# 2.net
KiCad netlist of a schematic drawn in Altium Designer
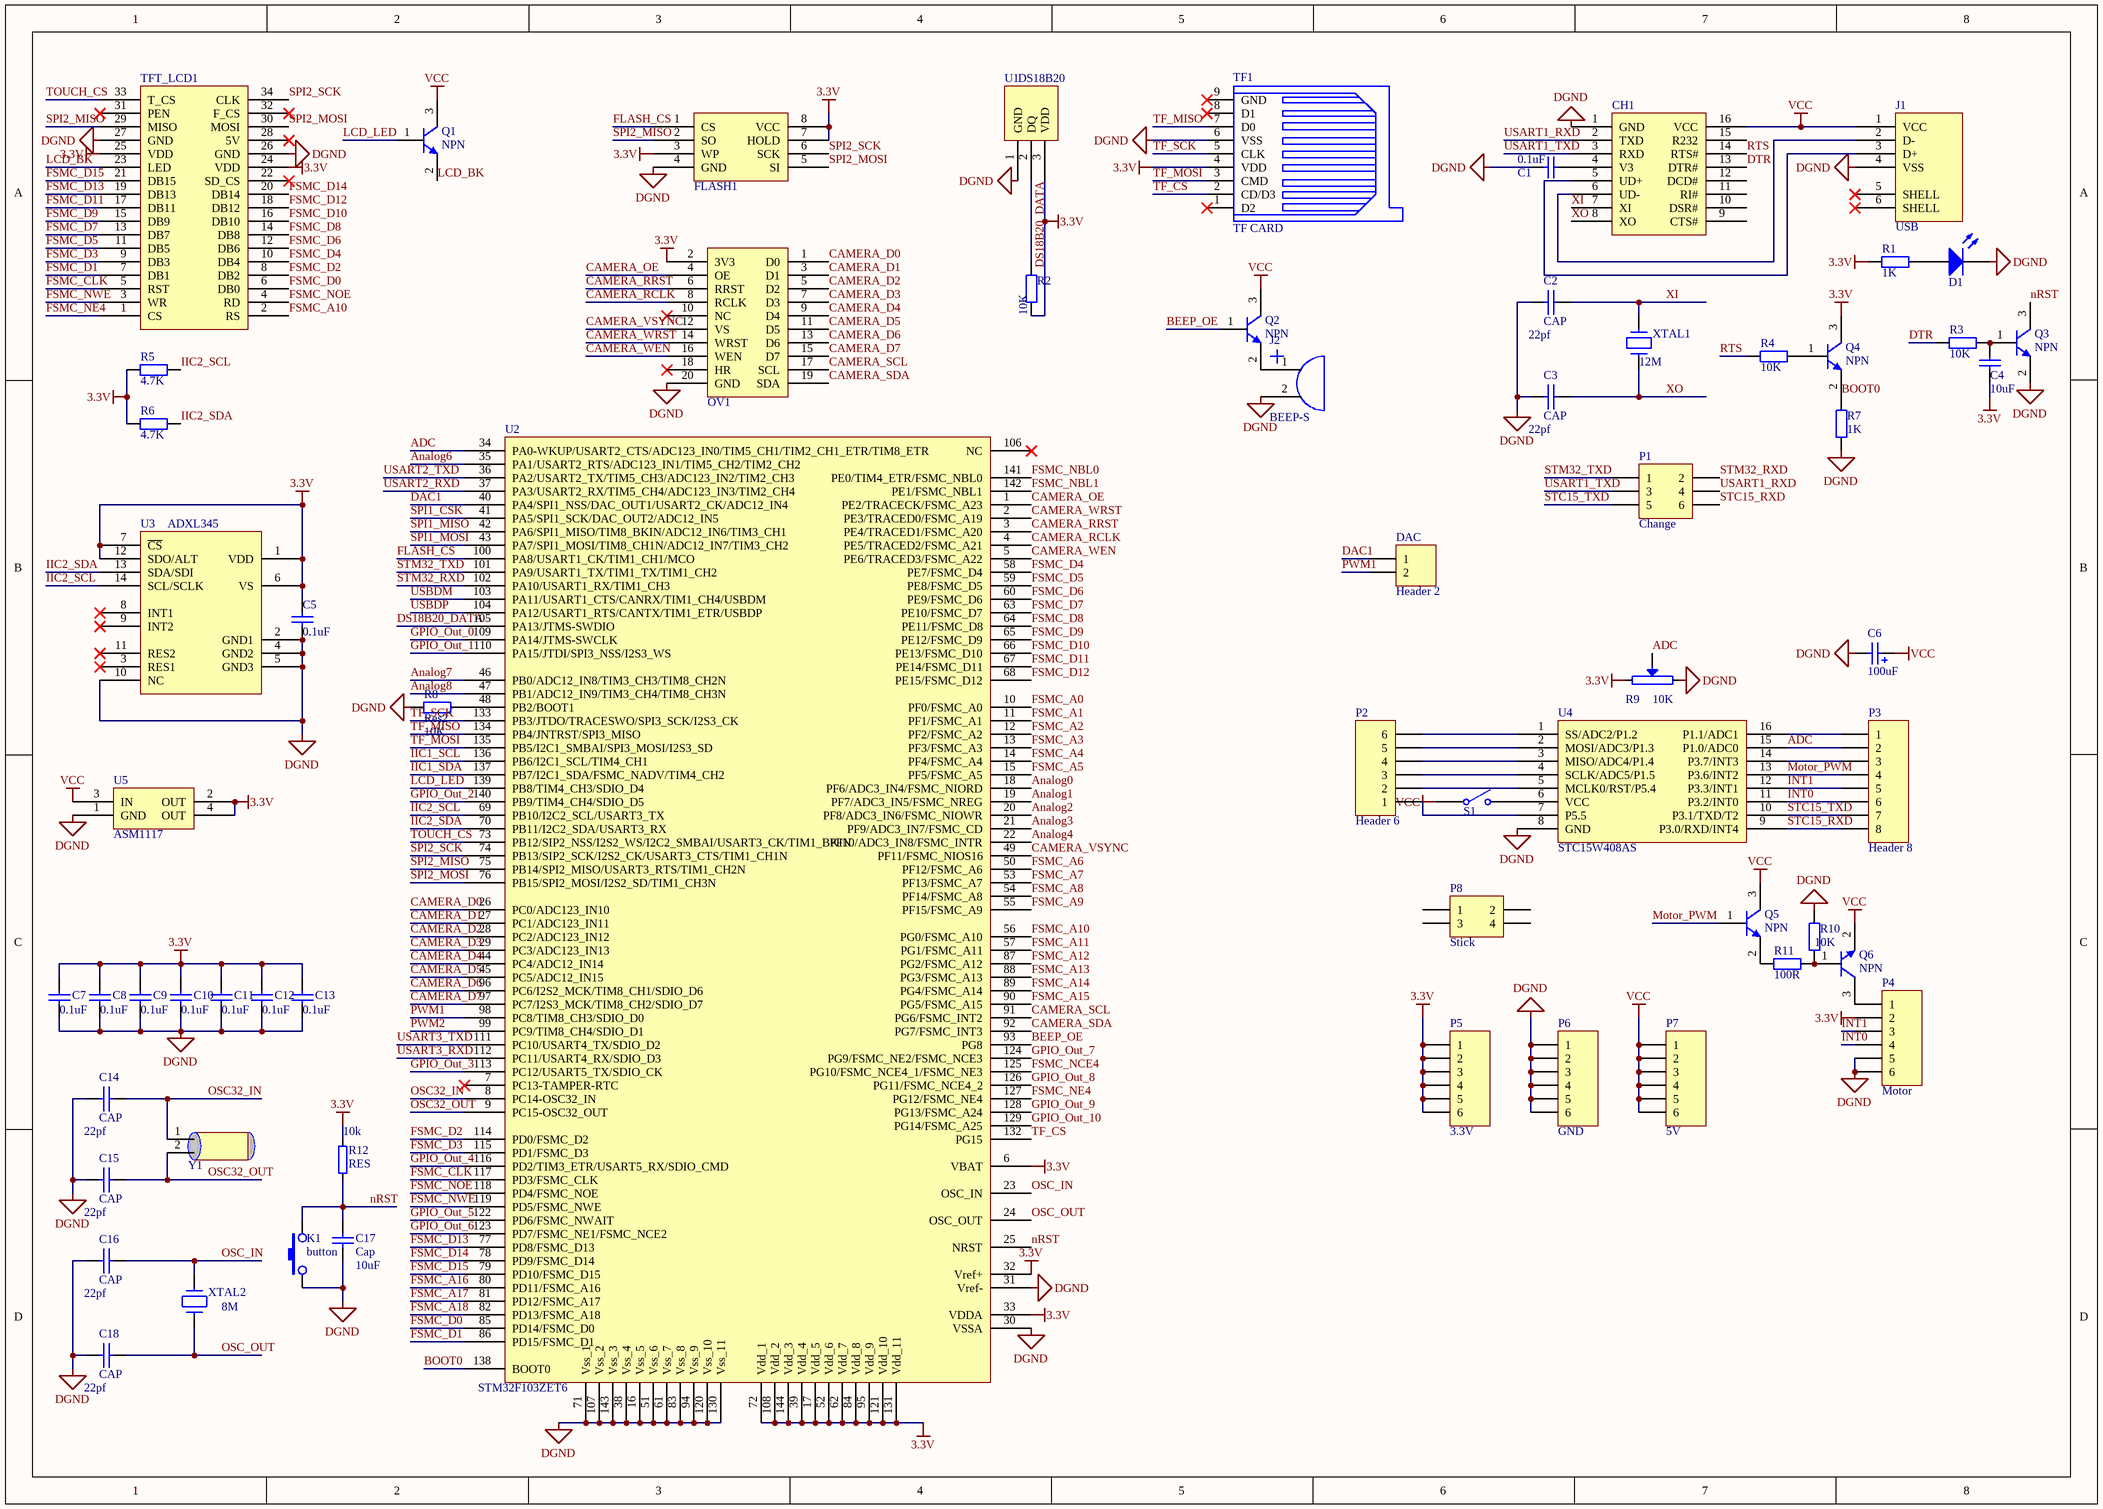
[diagram p0: 测试板2.SchDoc]

(export (version "E")
  (design (tool "Eeschema 10.0.6"))
  (components
    (comp (ref "C1")
      (value "0.1uF")
      (footprint "0805")
      (description "Capacitor")
      (fields (field (name "Comment") "Cap") (field (name "PUBLISHER") "Altium Limited"))
      (libsource (lib "Miscellaneous Devices") (part "Cap"))
    )
    (comp (ref "C2")
      (value "CAP")
      (footprint "0805")
      (fields (field (name "ALTIUM_VALUE") "22pf"))
      (libsource (lib "常用元件库") (part "CAP"))
    )
    (comp (ref "C3")
      (value "CAP")
      (footprint "0805")
      (fields (field (name "ALTIUM_VALUE") "22pf"))
      (libsource (lib "常用元件库") (part "CAP"))
    )
    (comp (ref "C4")
      (value "10uF")
      (footprint "1206")
      (description "Capacitor")
      (fields (field (name "Comment") "Cap") (field (name "PUBLISHER") "Altium Limited"))
      (libsource (lib "Miscellaneous Devices") (part "Cap"))
    )
    (comp (ref "C5")
      (value "0.1uF")
      (footprint "0805")
      (description "Capacitor")
      (fields (field (name "Comment") "Cap") (field (name "PUBLISHER") "Altium Limited"))
      (libsource (lib "Miscellaneous Devices") (part "Cap"))
    )
    (comp (ref "C6")
      (value "100uF")
      (footprint "RB.1/.3")
      (description "Polarized Capacitor (Axial)")
      (fields (field (name "Comment") "Cap Pol2") (field (name "PUBLISHER") "Altium Limited"))
      (libsource (lib "Miscellaneous Devices") (part "Cap Pol2"))
    )
    (comp (ref "C7")
      (value "0.1uF")
      (footprint "0805")
      (description "Capacitor")
      (fields (field (name "Comment") "Cap") (field (name "PUBLISHER") "Altium Limited"))
      (libsource (lib "Miscellaneous Devices") (part "Cap"))
    )
    (comp (ref "C8")
      (value "0.1uF")
      (footprint "0805")
      (description "Capacitor")
      (fields (field (name "Comment") "Cap") (field (name "PUBLISHER") "Altium Limited"))
      (libsource (lib "Miscellaneous Devices") (part "Cap"))
    )
    (comp (ref "C9")
      (value "0.1uF")
      (footprint "0805")
      (description "Capacitor")
      (fields (field (name "Comment") "Cap") (field (name "PUBLISHER") "Altium Limited"))
      (libsource (lib "Miscellaneous Devices") (part "Cap"))
    )
    (comp (ref "C10")
      (value "0.1uF")
      (footprint "0805")
      (description "Capacitor")
      (fields (field (name "Comment") "Cap") (field (name "PUBLISHER") "Altium Limited"))
      (libsource (lib "Miscellaneous Devices") (part "Cap"))
    )
    (comp (ref "C11")
      (value "0.1uF")
      (footprint "0805")
      (description "Capacitor")
      (fields (field (name "Comment") "Cap") (field (name "PUBLISHER") "Altium Limited"))
      (libsource (lib "Miscellaneous Devices") (part "Cap"))
    )
    (comp (ref "C12")
      (value "0.1uF")
      (footprint "0805")
      (description "Capacitor")
      (fields (field (name "Comment") "Cap") (field (name "PUBLISHER") "Altium Limited"))
      (libsource (lib "Miscellaneous Devices") (part "Cap"))
    )
    (comp (ref "C13")
      (value "0.1uF")
      (footprint "0805")
      (description "Capacitor")
      (fields (field (name "Comment") "Cap") (field (name "PUBLISHER") "Altium Limited"))
      (libsource (lib "Miscellaneous Devices") (part "Cap"))
    )
    (comp (ref "C14")
      (value "CAP")
      (footprint "0805")
      (fields (field (name "ALTIUM_VALUE") "22pf"))
      (libsource (lib "常用元件库") (part "CAP"))
    )
    (comp (ref "C15")
      (value "CAP")
      (footprint "0805")
      (fields (field (name "ALTIUM_VALUE") "22pf"))
      (libsource (lib "常用元件库") (part "CAP"))
    )
    (comp (ref "C16")
      (value "CAP")
      (footprint "0805")
      (fields (field (name "ALTIUM_VALUE") "22pf"))
      (libsource (lib "常用元件库") (part "CAP"))
    )
    (comp (ref "C17")
      (value "Cap")
      (footprint "1206")
      (description "Capacitor")
      (fields (field (name "ALTIUM_VALUE") "10uF") (field (name "PUBLISHER") "Altium Limited"))
      (libsource (lib "Miscellaneous Devices") (part "Cap"))
    )
    (comp (ref "C18")
      (value "CAP")
      (footprint "0805")
      (fields (field (name "ALTIUM_VALUE") "22pf"))
      (libsource (lib "常用元件库") (part "CAP"))
    )
    (comp (ref "CH1")
      (value "Component_1")
      (footprint "SOIC127P600X170-16N")
      (libsource (lib "CH340G") (part "Component_1"))
    )
    (comp (ref "D1")
      (value "LED0")
      (footprint "LED-0805")
      (description "发光二极管")
      (fields (field (name "PUBLISHER") "Altium Limited"))
      (libsource (lib "fszhang") (part "LED0"))
    )
    (comp (ref "DAC")
      (value "Header 2")
      (footprint "HDR1X2")
      (description "Header, 2-Pin")
      (fields (field (name "PUBLISHER") "Altium Limited"))
      (libsource (lib "Miscellaneous Connectors") (part "Header 2"))
    )
    (comp (ref "FLASH1") (value "W25Q64") (footprint "8S2_L") (libsource (lib "显示屏及摄像头") (part "W25Q64")))
    (comp (ref "J1")
      (value "USB")
      (footprint "USB_B1")
      (description "USB接口")
      (libsource (lib "HDR_fszhang") (part "USB"))
    )
    (comp (ref "J2")
      (value "BEEP-S")
      (footprint "BEEP-S")
      (description "有源蜂鸣器")
      (libsource (lib "fszhang") (part "BEEP-S"))
    )
    (comp (ref "K1") (value "button") (footprint "SW_PB4_A1") (libsource (lib "my Library") (part "button")))
    (comp (ref "OV1")
      (value "OV7725摄像头")
      (footprint "HDR2X10")
      (libsource (lib "显示屏及摄像头") (part "OV7725摄像头"))
    )
    (comp (ref "P1")
      (value "Change")
      (footprint "HDR2X3")
      (description "Header, 3-Pin, Dual row")
      (fields (field (name "PUBLISHER") "Altium Limited"))
      (libsource (lib "Miscellaneous Connectors") (part "Header 3X2"))
    )
    (comp (ref "P2")
      (value "Header 6")
      (footprint "HDR1X6")
      (description "Header, 6-Pin")
      (fields (field (name "PUBLISHER") "Altium Limited"))
      (libsource (lib "") (part "Header 6_1"))
    )
    (comp (ref "P3")
      (value "Header 8")
      (footprint "HDR1X8")
      (description "Header, 8-Pin")
      (fields (field (name "PUBLISHER") "Altium Limited"))
      (libsource (lib "Miscellaneous Connectors") (part "Header 8"))
    )
    (comp (ref "P4")
      (value "Motor")
      (footprint "HDR1X6")
      (description "Header, 6-Pin")
      (fields (field (name "PUBLISHER") "Altium Limited"))
      (libsource (lib "Miscellaneous Connectors") (part "Header 6"))
    )
    (comp (ref "P5")
      (value "3.3V")
      (footprint "HDR1X6")
      (description "Header, 6-Pin")
      (fields (field (name "PUBLISHER") "Altium Limited"))
      (libsource (lib "Miscellaneous Connectors") (part "Header 6"))
    )
    (comp (ref "P6")
      (value "GND")
      (footprint "HDR1X6")
      (description "Header, 6-Pin")
      (fields (field (name "PUBLISHER") "Altium Limited"))
      (libsource (lib "Miscellaneous Connectors") (part "Header 6"))
    )
    (comp (ref "P7")
      (value "5V")
      (footprint "HDR1X6")
      (description "Header, 6-Pin")
      (fields (field (name "PUBLISHER") "Altium Limited"))
      (libsource (lib "Miscellaneous Connectors") (part "Header 6"))
    )
    (comp (ref "P8")
      (value "Stick")
      (footprint "HDR2X2")
      (description "Header, 2-Pin, Dual row")
      (fields (field (name "PUBLISHER") "Altium Limited"))
      (libsource (lib "Miscellaneous Connectors") (part "Header 2X2"))
    )
    (comp (ref "Q1")
      (value "NPN")
      (footprint "SOT23-3")
      (description "贴片三极管")
      (fields (field (name "PUBLISHER") "Altium Limited"))
      (libsource (lib "fszhang") (part "NPN1"))
    )
    (comp (ref "Q2")
      (value "NPN")
      (footprint "SOT23-3")
      (description "贴片三极管")
      (fields (field (name "PUBLISHER") "Altium Limited"))
      (libsource (lib "fszhang") (part "NPN1"))
    )
    (comp (ref "Q3")
      (value "NPN")
      (footprint "SOT23-3")
      (description "贴片三极管")
      (fields (field (name "PUBLISHER") "Altium Limited"))
      (libsource (lib "fszhang") (part "NPN1"))
    )
    (comp (ref "Q4")
      (value "NPN")
      (footprint "SOT23-3")
      (description "贴片三极管")
      (fields (field (name "PUBLISHER") "Altium Limited"))
      (libsource (lib "fszhang") (part "NPN1"))
    )
    (comp (ref "Q5")
      (value "NPN")
      (footprint "SOT23-3")
      (description "贴片三极管")
      (fields (field (name "PUBLISHER") "Altium Limited"))
      (libsource (lib "fszhang") (part "NPN1"))
    )
    (comp (ref "Q6")
      (value "NPN")
      (footprint "SOT89N")
      (description "贴片三极管")
      (fields (field (name "PUBLISHER") "Altium Limited"))
      (libsource (lib "fszhang") (part "NPN1"))
    )
    (comp (ref "R1")
      (value "1K")
      (footprint "0805")
      (description "Resistor")
      (fields (field (name "Comment") "Res2") (field (name "PUBLISHER") "Altium Limited"))
      (libsource (lib "Miscellaneous Devices") (part "Res2"))
    )
    (comp (ref "R2")
      (value "10K")
      (footprint "0805")
      (description "Resistor")
      (fields (field (name "Comment") "Res2") (field (name "PUBLISHER") "Altium Limited"))
      (libsource (lib "") (part "Res2_1"))
    )
    (comp (ref "R3")
      (value "10K")
      (footprint "0805")
      (description "Resistor")
      (fields (field (name "Comment") "Res2") (field (name "PUBLISHER") "Altium Limited"))
      (libsource (lib "") (part "Res2_2"))
    )
    (comp (ref "R4")
      (value "10K")
      (footprint "0805")
      (description "Resistor")
      (fields (field (name "Comment") "Res2") (field (name "PUBLISHER") "Altium Limited"))
      (libsource (lib "") (part "Res2_2"))
    )
    (comp (ref "R5")
      (value "4.7K")
      (footprint "0805")
      (description "Resistor")
      (fields (field (name "Comment") "Res2") (field (name "PUBLISHER") "Altium Limited"))
      (libsource (lib "Miscellaneous Devices") (part "Res2"))
    )
    (comp (ref "R6")
      (value "4.7K")
      (footprint "0805")
      (description "Resistor")
      (fields (field (name "Comment") "Res2") (field (name "PUBLISHER") "Altium Limited"))
      (libsource (lib "Miscellaneous Devices") (part "Res2"))
    )
    (comp (ref "R7")
      (value "1K")
      (footprint "0805")
      (description "Resistor")
      (fields (field (name "Comment") "Res2") (field (name "PUBLISHER") "Altium Limited"))
      (libsource (lib "") (part "Res2_1"))
    )
    (comp (ref "R8")
      (value "Res2")
      (footprint "0805")
      (description "Resistor")
      (fields (field (name "ALTIUM_VALUE") "10K") (field (name "PUBLISHER") "Altium Limited"))
      (libsource (lib "Miscellaneous Devices") (part "Res2"))
    )
    (comp (ref "R9") (value "10K") (footprint "RVR-2") (libsource (lib "常用元件库") (part "VR")))
    (comp (ref "R10")
      (value "10K")
      (footprint "0805")
      (description "Resistor")
      (fields (field (name "Comment") "Res2") (field (name "PUBLISHER") "Altium Limited"))
      (libsource (lib "") (part "Res2_3"))
    )
    (comp (ref "R11")
      (value "100R")
      (footprint "0805")
      (description "Resistor")
      (fields (field (name "Comment") "Res2") (field (name "PUBLISHER") "Altium Limited"))
      (libsource (lib "Miscellaneous Devices") (part "Res2"))
    )
    (comp (ref "R12")
      (value "RES")
      (footprint "0805")
      (fields (field (name "ALTIUM_VALUE") "10k"))
      (libsource (lib "电阻") (part "RES"))
    )
    (comp (ref "S1")
      (value "SW-SPST")
      (footprint "SWITCH_B1")
      (description "Single-Pole, Single-Throw Switch")
      (fields (field (name "PUBLISHER") "Altium Limited"))
      (libsource (lib "Miscellaneous Devices") (part "SW-SPST"))
    )
    (comp (ref "TF1")
      (value "TF CARD")
      (footprint "TFP09-2-12B")
      (libsource (lib "My Footprint") (part "TF CARD"))
    )
    (comp (ref "TFT_LCD1")
      (value "Component_1")
      (footprint "HDR2X17")
      (libsource (lib "显示屏") (part "Component_1"))
    )
    (comp (ref "U1")
      (value "DS18B20")
      (footprint "TO-92A")
      (description "温度传感器")
      (libsource (lib "fszhang") (part "DS18B20"))
    )
    (comp (ref "U2")
      (value "STM32F103ZET6")
      (footprint "TQFP-144")
      (libsource (lib "STM32F103ZET6") (part "STM32F103ZET6"))
    )
    (comp (ref "U3")
      (value "ADXL345")
      (footprint "ADXL345:PCBComponent_1")
      (libsource (lib "ADXL345") (part "ADXL345"))
    )
    (comp (ref "U4")
      (value "STC15W408AS")
      (footprint "SOIC127P600X170-16N")
      (libsource (lib "显示屏及摄像头") (part "STC15W408AS"))
    )
    (comp (ref "U5")
      (value "ASM1117")
      (footprint "SOT223")
      (description "3.3V稳压芯片")
      (libsource (lib "fszhang") (part "ASM1117"))
    )
    (comp (ref "XTAL1")
      (value "12M")
      (footprint "X-SM49")
      (fields (field (name "Comment") "CRYSTAL"))
      (libsource (lib "常用元件库") (part "CRYSTAL"))
    )
    (comp (ref "XTAL2")
      (value "8M")
      (footprint "X-SM49")
      (fields (field (name "Comment") "CRYSTAL"))
      (libsource (lib "常用元件库") (part "CRYSTAL"))
    )
    (comp (ref "Y1") (value "32K晶振") (footprint "X-TC15") (libsource (lib "Library 1") (part "32K晶振")))
  )
  (nets
    (net (code "1") (name "/ADC") (class "Default")
      (node (ref "P3") (pin "2") (pinfunction "2_2") (pintype "passive"))
      (node (ref "R9") (pin "W") (pintype "passive"))
      (node (ref "U2") (pin "34") (pinfunction "PA0-WKUP/USART2_CTS/ADC123_IN0/TIM5_CH1/TIM2_CH1_ETR/TIM8_ETR_34") (pintype "passive"))
      (node (ref "U4") (pin "15") (pinfunction "P1.0/ADC0_15") (pintype "passive"))
    )
    (net (code "2") (name "/Analog0") (class "Default")
      (node (ref "U2") (pin "18") (pinfunction "PF6/ADC3_IN4/FSMC_NIORD_18") (pintype "passive"))
    )
    (net (code "3") (name "/Analog1") (class "Default")
      (node (ref "U2") (pin "19") (pinfunction "PF7/ADC3_IN5/FSMC_NREG_19") (pintype "passive"))
    )
    (net (code "4") (name "/Analog2") (class "Default")
      (node (ref "U2") (pin "20") (pinfunction "PF8/ADC3_IN6/FSMC_NIOWR_20") (pintype "passive"))
    )
    (net (code "5") (name "/Analog3") (class "Default")
      (node (ref "U2") (pin "21") (pinfunction "PF9/ADC3_IN7/FSMC_CD_21") (pintype "passive"))
    )
    (net (code "6") (name "/Analog4") (class "Default")
      (node (ref "U2") (pin "22") (pinfunction "PF10/ADC3_IN8/FSMC_INTR_22") (pintype "passive"))
    )
    (net (code "7") (name "/Analog6") (class "Default")
      (node (ref "U2") (pin "35") (pinfunction "PA1/USART2_RTS/ADC123_IN1/TIM5_CH2/TIM2_CH2_35") (pintype "passive"))
    )
    (net (code "8") (name "/Analog7") (class "Default")
      (node (ref "U2") (pin "46") (pinfunction "PB0/ADC12_IN8/TIM3_CH3/TIM8_CH2N_46") (pintype "passive"))
    )
    (net (code "9") (name "/Analog8") (class "Default")
      (node (ref "U2") (pin "47") (pinfunction "PB1/ADC12_IN9/TIM3_CH4/TIM8_CH3N_47") (pintype "passive"))
    )
    (net (code "10") (name "/BEEP_OE") (class "Default")
      (node (ref "Q2") (pin "1") (pinfunction "B_1") (pintype "passive"))
      (node (ref "U2") (pin "93") (pinfunction "PG8_93") (pintype "passive"))
    )
    (net (code "11") (name "/BOOT0") (class "Default")
      (node (ref "Q4") (pin "2") (pinfunction "E_2") (pintype "passive"))
      (node (ref "R7") (pin "2") (pinfunction "2_2") (pintype "passive"))
      (node (ref "U2") (pin "138") (pinfunction "BOOT0_138") (pintype "passive"))
    )
    (net (code "12") (name "/CAMERA_D0") (class "Default")
      (node (ref "OV1") (pin "1") (pinfunction "D0_1") (pintype "passive"))
      (node (ref "U2") (pin "26") (pinfunction "PC0/ADC123_IN10_26") (pintype "passive"))
    )
    (net (code "13") (name "/CAMERA_D1") (class "Default")
      (node (ref "OV1") (pin "3") (pinfunction "D1_3") (pintype "passive"))
      (node (ref "U2") (pin "27") (pinfunction "PC1/ADC123_IN11_27") (pintype "passive"))
    )
    (net (code "14") (name "/CAMERA_D2") (class "Default")
      (node (ref "OV1") (pin "5") (pinfunction "D2_5") (pintype "passive"))
      (node (ref "U2") (pin "28") (pinfunction "PC2/ADC123_IN12_28") (pintype "passive"))
    )
    (net (code "15") (name "/CAMERA_D3") (class "Default")
      (node (ref "OV1") (pin "7") (pinfunction "D3_7") (pintype "passive"))
      (node (ref "U2") (pin "29") (pinfunction "PC3/ADC123_IN13_29") (pintype "passive"))
    )
    (net (code "16") (name "/CAMERA_D4") (class "Default")
      (node (ref "OV1") (pin "9") (pinfunction "D4_9") (pintype "passive"))
      (node (ref "U2") (pin "44") (pinfunction "PC4/ADC12_IN14_44") (pintype "passive"))
    )
    (net (code "17") (name "/CAMERA_D5") (class "Default")
      (node (ref "OV1") (pin "11") (pinfunction "D5_11") (pintype "passive"))
      (node (ref "U2") (pin "45") (pinfunction "PC5/ADC12_IN15_45") (pintype "passive"))
    )
    (net (code "18") (name "/CAMERA_D6") (class "Default")
      (node (ref "OV1") (pin "13") (pinfunction "D6_13") (pintype "passive"))
      (node (ref "U2") (pin "96") (pinfunction "PC6/I2S2_MCK/TIM8_CH1/SDIO_D6_96") (pintype "passive"))
    )
    (net (code "19") (name "/CAMERA_D7") (class "Default")
      (node (ref "OV1") (pin "15") (pinfunction "D7_15") (pintype "passive"))
      (node (ref "U2") (pin "97") (pinfunction "PC7/I2S3_MCK/TIM8_CH2/SDIO_D7_97") (pintype "passive"))
    )
    (net (code "20") (name "/CAMERA_OE") (class "Default")
      (node (ref "OV1") (pin "4") (pinfunction "OE_4") (pintype "passive"))
      (node (ref "U2") (pin "1") (pinfunction "PE2/TRACECK/FSMC_A23_1") (pintype "passive"))
    )
    (net (code "21") (name "/CAMERA_RCLK") (class "Default")
      (node (ref "OV1") (pin "8") (pinfunction "RCLK_8") (pintype "passive"))
      (node (ref "U2") (pin "4") (pinfunction "PE5/TRACED2/FSMC_A21_4") (pintype "passive"))
    )
    (net (code "22") (name "/CAMERA_RRST") (class "Default")
      (node (ref "OV1") (pin "6") (pinfunction "RRST_6") (pintype "passive"))
      (node (ref "U2") (pin "3") (pinfunction "PE4/TRACED1/FSMC_A20_3") (pintype "passive"))
    )
    (net (code "23") (name "/CAMERA_SCL") (class "Default")
      (node (ref "OV1") (pin "17") (pinfunction "SCL_17") (pintype "passive"))
      (node (ref "U2") (pin "91") (pinfunction "PG6/FSMC_INT2_91") (pintype "passive"))
    )
    (net (code "24") (name "/CAMERA_SDA") (class "Default")
      (node (ref "OV1") (pin "19") (pinfunction "SDA_19") (pintype "passive"))
      (node (ref "U2") (pin "92") (pinfunction "PG7/FSMC_INT3_92") (pintype "passive"))
    )
    (net (code "25") (name "/CAMERA_VSYNC") (class "Default")
      (node (ref "OV1") (pin "12") (pinfunction "VS_12") (pintype "passive"))
      (node (ref "U2") (pin "49") (pinfunction "PF11/FSMC_NIOS16_49") (pintype "passive"))
    )
    (net (code "26") (name "/CAMERA_WEN") (class "Default")
      (node (ref "OV1") (pin "16") (pinfunction "WEN_16") (pintype "passive"))
      (node (ref "U2") (pin "5") (pinfunction "PE6/TRACED3/FSMC_A22_5") (pintype "passive"))
    )
    (net (code "27") (name "/CAMERA_WRST") (class "Default")
      (node (ref "OV1") (pin "14") (pinfunction "WRST_14") (pintype "passive"))
      (node (ref "U2") (pin "2") (pinfunction "PE3/TRACED0/FSMC_A19_2") (pintype "passive"))
    )
    (net (code "28") (name "/DAC1") (class "Default")
      (node (ref "DAC") (pin "1") (pinfunction "1_1") (pintype "passive"))
      (node (ref "U2") (pin "40") (pinfunction "PA4/SPI1_NSS/DAC_OUT1/USART2_CK/ADC12_IN4_40") (pintype "passive"))
    )
    (net (code "29") (name "/DS18B20_DATA") (class "Default")
      (node (ref "R2") (pin "2") (pinfunction "2_2") (pintype "passive"))
      (node (ref "U1") (pin "2") (pinfunction "DQ_2") (pintype "passive"))
      (node (ref "U2") (pin "105") (pinfunction "PA13/JTMS-SWDIO_105") (pintype "passive"))
    )
    (net (code "30") (name "/DTR") (class "Default")
      (node (ref "CH1") (pin "13") (pinfunction "DTR#_13") (pintype "passive"))
      (node (ref "R3") (pin "2") (pinfunction "2_2") (pintype "passive"))
    )
    (net (code "31") (name "/FLASH_CS") (class "Default")
      (node (ref "FLASH1") (pin "1") (pinfunction "CS_1") (pintype "passive"))
      (node (ref "U2") (pin "100") (pinfunction "PA8/USART1_CK/TIM1_CH1/MCO_100") (pintype "passive"))
    )
    (net (code "32") (name "/FSMC_A0") (class "Default")
      (node (ref "U2") (pin "10") (pinfunction "PF0/FSMC_A0_10") (pintype "passive"))
    )
    (net (code "33") (name "/FSMC_A1") (class "Default")
      (node (ref "U2") (pin "11") (pinfunction "PF1/FSMC_A1_11") (pintype "passive"))
    )
    (net (code "34") (name "/FSMC_A2") (class "Default")
      (node (ref "U2") (pin "12") (pinfunction "PF2/FSMC_A2_12") (pintype "passive"))
    )
    (net (code "35") (name "/FSMC_A3") (class "Default")
      (node (ref "U2") (pin "13") (pinfunction "PF3/FSMC_A3_13") (pintype "passive"))
    )
    (net (code "36") (name "/FSMC_A4") (class "Default")
      (node (ref "U2") (pin "14") (pinfunction "PF4/FSMC_A4_14") (pintype "passive"))
    )
    (net (code "37") (name "/FSMC_A5") (class "Default")
      (node (ref "U2") (pin "15") (pinfunction "PF5/FSMC_A5_15") (pintype "passive"))
    )
    (net (code "38") (name "/FSMC_A6") (class "Default")
      (node (ref "U2") (pin "50") (pinfunction "PF12/FSMC_A6_50") (pintype "passive"))
    )
    (net (code "39") (name "/FSMC_A7") (class "Default")
      (node (ref "U2") (pin "53") (pinfunction "PF13/FSMC_A7_53") (pintype "passive"))
    )
    (net (code "40") (name "/FSMC_A8") (class "Default")
      (node (ref "U2") (pin "54") (pinfunction "PF14/FSMC_A8_54") (pintype "passive"))
    )
    (net (code "41") (name "/FSMC_A9") (class "Default")
      (node (ref "U2") (pin "55") (pinfunction "PF15/FSMC_A9_55") (pintype "passive"))
    )
    (net (code "42") (name "/FSMC_A10") (class "Default")
      (node (ref "TFT_LCD1") (pin "2") (pinfunction "RS_2") (pintype "passive"))
      (node (ref "U2") (pin "56") (pinfunction "PG0/FSMC_A10_56") (pintype "passive"))
    )
    (net (code "43") (name "/FSMC_A11") (class "Default")
      (node (ref "U2") (pin "57") (pinfunction "PG1/FSMC_A11_57") (pintype "passive"))
    )
    (net (code "44") (name "/FSMC_A12") (class "Default")
      (node (ref "U2") (pin "87") (pinfunction "PG2/FSMC_A12_87") (pintype "passive"))
    )
    (net (code "45") (name "/FSMC_A13") (class "Default")
      (node (ref "U2") (pin "88") (pinfunction "PG3/FSMC_A13_88") (pintype "passive"))
    )
    (net (code "46") (name "/FSMC_A14") (class "Default")
      (node (ref "U2") (pin "89") (pinfunction "PG4/FSMC_A14_89") (pintype "passive"))
    )
    (net (code "47") (name "/FSMC_A15") (class "Default")
      (node (ref "U2") (pin "90") (pinfunction "PG5/FSMC_A15_90") (pintype "passive"))
    )
    (net (code "48") (name "/FSMC_A16") (class "Default")
      (node (ref "U2") (pin "80") (pinfunction "PD11/FSMC_A16_80") (pintype "passive"))
    )
    (net (code "49") (name "/FSMC_A17") (class "Default")
      (node (ref "U2") (pin "81") (pinfunction "PD12/FSMC_A17_81") (pintype "passive"))
    )
    (net (code "50") (name "/FSMC_A18") (class "Default")
      (node (ref "U2") (pin "82") (pinfunction "PD13/FSMC_A18_82") (pintype "passive"))
    )
    (net (code "51") (name "/FSMC_CLK") (class "Default")
      (node (ref "TFT_LCD1") (pin "5") (pinfunction "RST_5") (pintype "passive"))
      (node (ref "U2") (pin "117") (pinfunction "PD3/FSMC_CLK_117") (pintype "passive"))
    )
    (net (code "52") (name "/FSMC_D0") (class "Default")
      (node (ref "TFT_LCD1") (pin "6") (pinfunction "DB0_6") (pintype "passive"))
      (node (ref "U2") (pin "85") (pinfunction "PD14/FSMC_D0_85") (pintype "passive"))
    )
    (net (code "53") (name "/FSMC_D1") (class "Default")
      (node (ref "TFT_LCD1") (pin "7") (pinfunction "DB1_7") (pintype "passive"))
      (node (ref "U2") (pin "86") (pinfunction "PD15/FSMC_D1_86") (pintype "passive"))
    )
    (net (code "54") (name "/FSMC_D2") (class "Default")
      (node (ref "TFT_LCD1") (pin "8") (pinfunction "DB2_8") (pintype "passive"))
      (node (ref "U2") (pin "114") (pinfunction "PD0/FSMC_D2_114") (pintype "passive"))
    )
    (net (code "55") (name "/FSMC_D3") (class "Default")
      (node (ref "TFT_LCD1") (pin "9") (pinfunction "DB3_9") (pintype "passive"))
      (node (ref "U2") (pin "115") (pinfunction "PD1/FSMC_D3_115") (pintype "passive"))
    )
    (net (code "56") (name "/FSMC_D4") (class "Default")
      (node (ref "TFT_LCD1") (pin "10") (pinfunction "DB4_10") (pintype "passive"))
      (node (ref "U2") (pin "58") (pinfunction "PE7/FSMC_D4_58") (pintype "passive"))
    )
    (net (code "57") (name "/FSMC_D5") (class "Default")
      (node (ref "TFT_LCD1") (pin "11") (pinfunction "DB5_11") (pintype "passive"))
      (node (ref "U2") (pin "59") (pinfunction "PE8/FSMC_D5_59") (pintype "passive"))
    )
    (net (code "58") (name "/FSMC_D6") (class "Default")
      (node (ref "TFT_LCD1") (pin "12") (pinfunction "DB6_12") (pintype "passive"))
      (node (ref "U2") (pin "60") (pinfunction "PE9/FSMC_D6_60") (pintype "passive"))
    )
    (net (code "59") (name "/FSMC_D7") (class "Default")
      (node (ref "TFT_LCD1") (pin "13") (pinfunction "DB7_13") (pintype "passive"))
      (node (ref "U2") (pin "63") (pinfunction "PE10/FSMC_D7_63") (pintype "passive"))
    )
    (net (code "60") (name "/FSMC_D8") (class "Default")
      (node (ref "TFT_LCD1") (pin "14") (pinfunction "DB8_14") (pintype "passive"))
      (node (ref "U2") (pin "64") (pinfunction "PE11/FSMC_D8_64") (pintype "passive"))
    )
    (net (code "61") (name "/FSMC_D9") (class "Default")
      (node (ref "TFT_LCD1") (pin "15") (pinfunction "DB9_15") (pintype "passive"))
      (node (ref "U2") (pin "65") (pinfunction "PE12/FSMC_D9_65") (pintype "passive"))
    )
    (net (code "62") (name "/FSMC_D10") (class "Default")
      (node (ref "TFT_LCD1") (pin "16") (pinfunction "DB10_16") (pintype "passive"))
      (node (ref "U2") (pin "66") (pinfunction "PE13/FSMC_D10_66") (pintype "passive"))
    )
    (net (code "63") (name "/FSMC_D11") (class "Default")
      (node (ref "TFT_LCD1") (pin "17") (pinfunction "DB11_17") (pintype "passive"))
      (node (ref "U2") (pin "67") (pinfunction "PE14/FSMC_D11_67") (pintype "passive"))
    )
    (net (code "64") (name "/FSMC_D12") (class "Default")
      (node (ref "TFT_LCD1") (pin "18") (pinfunction "DB12_18") (pintype "passive"))
      (node (ref "U2") (pin "68") (pinfunction "PE15/FSMC_D12_68") (pintype "passive"))
    )
    (net (code "65") (name "/FSMC_D13") (class "Default")
      (node (ref "TFT_LCD1") (pin "19") (pinfunction "DB13_19") (pintype "passive"))
      (node (ref "U2") (pin "77") (pinfunction "PD8/FSMC_D13_77") (pintype "passive"))
    )
    (net (code "66") (name "/FSMC_D14") (class "Default")
      (node (ref "TFT_LCD1") (pin "20") (pinfunction "DB14_20") (pintype "passive"))
      (node (ref "U2") (pin "78") (pinfunction "PD9/FSMC_D14_78") (pintype "passive"))
    )
    (net (code "67") (name "/FSMC_D15") (class "Default")
      (node (ref "TFT_LCD1") (pin "21") (pinfunction "DB15_21") (pintype "passive"))
      (node (ref "U2") (pin "79") (pinfunction "PD10/FSMC_D15_79") (pintype "passive"))
    )
    (net (code "68") (name "/FSMC_NBL0") (class "Default")
      (node (ref "U2") (pin "141") (pinfunction "PE0/TIM4_ETR/FSMC_NBL0_141") (pintype "passive"))
    )
    (net (code "69") (name "/FSMC_NBL1") (class "Default")
      (node (ref "U2") (pin "142") (pinfunction "PE1/FSMC_NBL1_142") (pintype "passive"))
    )
    (net (code "70") (name "/FSMC_NCE4") (class "Default")
      (node (ref "U2") (pin "125") (pinfunction "PG10/FSMC_NCE4_1/FSMC_NE3_125") (pintype "passive"))
    )
    (net (code "71") (name "/FSMC_NE4") (class "Default")
      (node (ref "TFT_LCD1") (pin "1") (pinfunction "CS_1") (pintype "passive"))
      (node (ref "U2") (pin "127") (pinfunction "PG12/FSMC_NE4_127") (pintype "passive"))
    )
    (net (code "72") (name "/FSMC_NOE") (class "Default")
      (node (ref "TFT_LCD1") (pin "4") (pinfunction "RD_4") (pintype "passive"))
      (node (ref "U2") (pin "118") (pinfunction "PD4/FSMC_NOE_118") (pintype "passive"))
    )
    (net (code "73") (name "/FSMC_NWE") (class "Default")
      (node (ref "TFT_LCD1") (pin "3") (pinfunction "WR_3") (pintype "passive"))
      (node (ref "U2") (pin "119") (pinfunction "PD5/FSMC_NWE_119") (pintype "passive"))
    )
    (net (code "74") (name "/GPIO_Out_0") (class "Default")
      (node (ref "U2") (pin "109") (pinfunction "PA14/JTMS-SWCLK_109") (pintype "passive"))
    )
    (net (code "75") (name "/GPIO_Out_1") (class "Default")
      (node (ref "U2") (pin "110") (pinfunction "PA15/JTDI/SPI3_NSS/I2S3_WS_110") (pintype "passive"))
    )
    (net (code "76") (name "/GPIO_Out_2") (class "Default")
      (node (ref "U2") (pin "140") (pinfunction "PB9/TIM4_CH4/SDIO_D5_140") (pintype "passive"))
    )
    (net (code "77") (name "/GPIO_Out_3") (class "Default")
      (node (ref "U2") (pin "113") (pinfunction "PC12/USART5_TX/SDIO_CK_113") (pintype "passive"))
    )
    (net (code "78") (name "/GPIO_Out_4") (class "Default")
      (node (ref "U2") (pin "116") (pinfunction "PD2/TIM3_ETR/USART5_RX/SDIO_CMD_116") (pintype "passive"))
    )
    (net (code "79") (name "/GPIO_Out_5") (class "Default")
      (node (ref "U2") (pin "122") (pinfunction "PD6/FSMC_NWAIT_122") (pintype "passive"))
    )
    (net (code "80") (name "/GPIO_Out_6") (class "Default")
      (node (ref "U2") (pin "123") (pinfunction "PD7/FSMC_NE1/FSMC_NCE2_123") (pintype "passive"))
    )
    (net (code "81") (name "/GPIO_Out_7") (class "Default")
      (node (ref "U2") (pin "124") (pinfunction "PG9/FSMC_NE2/FSMC_NCE3_124") (pintype "passive"))
    )
    (net (code "82") (name "/GPIO_Out_8") (class "Default")
      (node (ref "U2") (pin "126") (pinfunction "PG11/FSMC_NCE4_2_126") (pintype "passive"))
    )
    (net (code "83") (name "/GPIO_Out_9") (class "Default")
      (node (ref "U2") (pin "128") (pinfunction "PG13/FSMC_A24_128") (pintype "passive"))
    )
    (net (code "84") (name "/GPIO_Out_10") (class "Default")
      (node (ref "U2") (pin "129") (pinfunction "PG14/FSMC_A25_129") (pintype "passive"))
    )
    (net (code "85") (name "/IIC1_SCL") (class "Default")
      (node (ref "U2") (pin "136") (pinfunction "PB6/I2C1_SCL/TIM4_CH1_136") (pintype "passive"))
    )
    (net (code "86") (name "/IIC1_SDA") (class "Default")
      (node (ref "U2") (pin "137") (pinfunction "PB7/I2C1_SDA/FSMC_NADV/TIM4_CH2_137") (pintype "passive"))
    )
    (net (code "87") (name "/IIC2_SCL") (class "Default")
      (node (ref "R5") (pin "2") (pinfunction "2_2") (pintype "passive"))
      (node (ref "U2") (pin "69") (pinfunction "PB10/I2C2_SCL/USART3_TX_69") (pintype "passive"))
      (node (ref "U3") (pin "14") (pinfunction "SCL/SCLK_14") (pintype "passive"))
    )
    (net (code "88") (name "/IIC2_SDA") (class "Default")
      (node (ref "R6") (pin "2") (pinfunction "2_2") (pintype "passive"))
      (node (ref "U2") (pin "70") (pinfunction "PB11/I2C2_SDA/USART3_RX_70") (pintype "passive"))
      (node (ref "U3") (pin "13") (pinfunction "SDA/SDI_13") (pintype "passive"))
    )
    (net (code "89") (name "/INT0") (class "Default")
      (node (ref "P3") (pin "6") (pinfunction "6_6") (pintype "passive"))
      (node (ref "P4") (pin "4") (pinfunction "4_4") (pintype "passive"))
      (node (ref "U4") (pin "11") (pinfunction "P3.2/INT0_11") (pintype "passive"))
    )
    (net (code "90") (name "/INT1") (class "Default")
      (node (ref "P3") (pin "5") (pinfunction "5_5") (pintype "passive"))
      (node (ref "P4") (pin "3") (pinfunction "3_3") (pintype "passive"))
      (node (ref "U4") (pin "12") (pinfunction "P3.3/INT1_12") (pintype "passive"))
    )
    (net (code "91") (name "/LCD_BK") (class "Default")
      (node (ref "Q1") (pin "2") (pinfunction "E_2") (pintype "passive"))
      (node (ref "TFT_LCD1") (pin "23") (pinfunction "LED_23") (pintype "passive"))
    )
    (net (code "92") (name "/LCD_LED") (class "Default")
      (node (ref "Q1") (pin "1") (pinfunction "B_1") (pintype "passive"))
      (node (ref "U2") (pin "139") (pinfunction "PB8/TIM4_CH3/SDIO_D4_139") (pintype "passive"))
    )
    (net (code "93") (name "/Motor_PWM") (class "Default")
      (node (ref "P3") (pin "4") (pinfunction "4_4") (pintype "passive"))
      (node (ref "Q5") (pin "1") (pinfunction "B_1") (pintype "passive"))
      (node (ref "U4") (pin "13") (pinfunction "P3.6/INT2_13") (pintype "passive"))
    )
    (net (code "94") (name "/OSC32_IN") (class "Default")
      (node (ref "C14") (pin "2") (pinfunction "2_2") (pintype "passive"))
      (node (ref "U2") (pin "8") (pinfunction "PC14-OSC32_IN_8") (pintype "passive"))
      (node (ref "Y1") (pin "1") (pinfunction "X1_1") (pintype "passive"))
    )
    (net (code "95") (name "/OSC32_OUT") (class "Default")
      (node (ref "C15") (pin "2") (pinfunction "2_2") (pintype "passive"))
      (node (ref "U2") (pin "9") (pinfunction "PC15-OSC32_OUT_9") (pintype "passive"))
      (node (ref "Y1") (pin "2") (pinfunction "X2_2") (pintype "passive"))
    )
    (net (code "96") (name "/OSC_IN") (class "Default")
      (node (ref "C16") (pin "2") (pinfunction "2_2") (pintype "passive"))
      (node (ref "U2") (pin "23") (pinfunction "OSC_IN_23") (pintype "passive"))
      (node (ref "XTAL2") (pin "2") (pinfunction "2_2") (pintype "passive"))
    )
    (net (code "97") (name "/OSC_OUT") (class "Default")
      (node (ref "C18") (pin "2") (pinfunction "2_2") (pintype "passive"))
      (node (ref "U2") (pin "24") (pinfunction "OSC_OUT_24") (pintype "passive"))
      (node (ref "XTAL2") (pin "1") (pinfunction "1_1") (pintype "passive"))
    )
    (net (code "98") (name "/PWM1") (class "Default")
      (node (ref "DAC") (pin "2") (pinfunction "2_2") (pintype "passive"))
      (node (ref "U2") (pin "98") (pinfunction "PC8/TIM8_CH3/SDIO_D0_98") (pintype "passive"))
    )
    (net (code "99") (name "/PWM2") (class "Default")
      (node (ref "U2") (pin "99") (pinfunction "PC9/TIM8_CH4/SDIO_D1_99") (pintype "passive"))
    )
    (net (code "100") (name "/RTS") (class "Default")
      (node (ref "CH1") (pin "14") (pinfunction "RTS#_14") (pintype "passive"))
      (node (ref "R4") (pin "2") (pinfunction "2_2") (pintype "passive"))
    )
    (net (code "101") (name "/SPI1_CSK") (class "Default")
      (node (ref "U2") (pin "41") (pinfunction "PA5/SPI1_SCK/DAC_OUT2/ADC12_IN5_41") (pintype "passive"))
    )
    (net (code "102") (name "/SPI1_MISO") (class "Default")
      (node (ref "U2") (pin "42") (pinfunction "PA6/SPI1_MISO/TIM8_BKIN/ADC12_IN6/TIM3_CH1_42") (pintype "passive"))
    )
    (net (code "103") (name "/SPI1_MOSI") (class "Default")
      (node (ref "U2") (pin "43") (pinfunction "PA7/SPI1_MOSI/TIM8_CH1N/ADC12_IN7/TIM3_CH2_43") (pintype "passive"))
    )
    (net (code "104") (name "/SPI2_MISO") (class "Default")
      (node (ref "FLASH1") (pin "2") (pinfunction "SO_2") (pintype "passive"))
      (node (ref "TFT_LCD1") (pin "29") (pinfunction "MISO_29") (pintype "passive"))
      (node (ref "U2") (pin "75") (pinfunction "PB14/SPI2_MISO/USART3_RTS/TIM1_CH2N_75") (pintype "passive"))
    )
    (net (code "105") (name "/SPI2_MOSI") (class "Default")
      (node (ref "FLASH1") (pin "5") (pinfunction "SI_5") (pintype "passive"))
      (node (ref "TFT_LCD1") (pin "30") (pinfunction "MOSI_30") (pintype "passive"))
      (node (ref "U2") (pin "76") (pinfunction "PB15/SPI2_MOSI/I2S2_SD/TIM1_CH3N_76") (pintype "passive"))
    )
    (net (code "106") (name "/SPI2_SCK") (class "Default")
      (node (ref "FLASH1") (pin "6") (pinfunction "SCK_6") (pintype "passive"))
      (node (ref "TFT_LCD1") (pin "34") (pinfunction "CLK_34") (pintype "passive"))
      (node (ref "U2") (pin "74") (pinfunction "PB13/SIP2_SCK/I2S2_CK/USART3_CTS/TIM1_CH1N_74") (pintype "passive"))
    )
    (net (code "107") (name "/STC15_RXD") (class "Default")
      (node (ref "P1") (pin "6") (pinfunction "6_6") (pintype "passive"))
      (node (ref "P3") (pin "8") (pinfunction "8_8") (pintype "passive"))
      (node (ref "U4") (pin "9") (pinfunction "P3.0/RXD/INT4_9") (pintype "passive"))
    )
    (net (code "108") (name "/STC15_TXD") (class "Default")
      (node (ref "P1") (pin "5") (pinfunction "5_5") (pintype "passive"))
      (node (ref "P3") (pin "7") (pinfunction "7_7") (pintype "passive"))
      (node (ref "U4") (pin "10") (pinfunction "P3.1/TXD/T2_10") (pintype "passive"))
    )
    (net (code "109") (name "/STM32_RXD") (class "Default")
      (node (ref "P1") (pin "2") (pinfunction "2_2") (pintype "passive"))
      (node (ref "U2") (pin "102") (pinfunction "PA10/USART1_RX/TIM1_CH3_102") (pintype "passive"))
    )
    (net (code "110") (name "/STM32_TXD") (class "Default")
      (node (ref "P1") (pin "1") (pinfunction "1_1") (pintype "passive"))
      (node (ref "U2") (pin "101") (pinfunction "PA9/USART1_TX/TIM1_TX/TIM1_CH2_101") (pintype "passive"))
    )
    (net (code "111") (name "/TF_CS") (class "Default")
      (node (ref "TF1") (pin "2") (pinfunction "CD/D3_2") (pintype "passive"))
      (node (ref "U2") (pin "132") (pinfunction "PG15_132") (pintype "passive"))
    )
    (net (code "112") (name "/TF_MISO") (class "Default")
      (node (ref "TF1") (pin "7") (pinfunction "D0_7") (pintype "passive"))
      (node (ref "U2") (pin "134") (pinfunction "PB4/JNTRST/SPI3_MISO_134") (pintype "passive"))
    )
    (net (code "113") (name "/TF_MOSI") (class "Default")
      (node (ref "TF1") (pin "3") (pinfunction "CMD_3") (pintype "passive"))
      (node (ref "U2") (pin "135") (pinfunction "PB5/I2C1_SMBAI/SPI3_MOSI/I2S3_SD_135") (pintype "passive"))
    )
    (net (code "114") (name "/TF_SCK") (class "Default")
      (node (ref "TF1") (pin "5") (pinfunction "CLK_5") (pintype "passive"))
      (node (ref "U2") (pin "133") (pinfunction "PB3/JTDO/TRACESWO/SPI3_SCK/I2S3_CK_133") (pintype "passive"))
    )
    (net (code "115") (name "/TOUCH_CS") (class "Default")
      (node (ref "TFT_LCD1") (pin "33") (pinfunction "T_CS_33") (pintype "passive"))
      (node (ref "U2") (pin "73") (pinfunction "PB12/SIP2_NSS/I2S2_WS/I2C2_SMBAI/USART3_CK/TIM1_BKIN_73") (pintype "passive"))
    )
    (net (code "116") (name "/USART1_RXD") (class "Default")
      (node (ref "CH1") (pin "2") (pinfunction "TXD_2") (pintype "passive"))
      (node (ref "P1") (pin "4") (pinfunction "4_4") (pintype "passive"))
    )
    (net (code "117") (name "/USART1_TXD") (class "Default")
      (node (ref "CH1") (pin "3") (pinfunction "RXD_3") (pintype "passive"))
      (node (ref "P1") (pin "3") (pinfunction "3_3") (pintype "passive"))
    )
    (net (code "118") (name "/USART2_RXD") (class "Default")
      (node (ref "U2") (pin "37") (pinfunction "PA3/USART2_RX/TIM5_CH4/ADC123_IN3/TIM2_CH4_37") (pintype "passive"))
    )
    (net (code "119") (name "/USART2_TXD") (class "Default")
      (node (ref "U2") (pin "36") (pinfunction "PA2/USART2_TX/TIM5_CH3/ADC123_IN2/TIM2_CH3_36") (pintype "passive"))
    )
    (net (code "120") (name "/USART3_RXD") (class "Default")
      (node (ref "U2") (pin "112") (pinfunction "PC11/USART4_RX/SDIO_D3_112") (pintype "passive"))
    )
    (net (code "121") (name "/USART3_TXD") (class "Default")
      (node (ref "U2") (pin "111") (pinfunction "PC10/USART4_TX/SDIO_D2_111") (pintype "passive"))
    )
    (net (code "122") (name "/USBDM") (class "Default")
      (node (ref "U2") (pin "103") (pinfunction "PA11/USART1_CTS/CANRX/TIM1_CH4/USBDM_103") (pintype "passive"))
    )
    (net (code "123") (name "/USBDP") (class "Default")
      (node (ref "U2") (pin "104") (pinfunction "PA12/USART1_RTS/CANTX/TIM1_ETR/USBDP_104") (pintype "passive"))
    )
    (net (code "124") (name "/XI") (class "Default")
      (node (ref "C2") (pin "2") (pinfunction "2_2") (pintype "passive"))
      (node (ref "CH1") (pin "7") (pinfunction "XI_7") (pintype "passive"))
      (node (ref "XTAL1") (pin "2") (pinfunction "2_2") (pintype "passive"))
    )
    (net (code "125") (name "/XO") (class "Default")
      (node (ref "C3") (pin "2") (pinfunction "2_2") (pintype "passive"))
      (node (ref "CH1") (pin "8") (pinfunction "XO_8") (pintype "passive"))
      (node (ref "XTAL1") (pin "1") (pinfunction "1_1") (pintype "passive"))
    )
    (net (code "126") (name "/nRST") (class "Default")
      (node (ref "C17") (pin "2") (pinfunction "2_2") (pintype "passive"))
      (node (ref "K1") (pin "2") (pinfunction "2_2") (pintype "passive"))
      (node (ref "Q3") (pin "3") (pinfunction "C_3") (pintype "passive"))
      (node (ref "R12") (pin "1") (pinfunction "1_1") (pintype "passive"))
      (node (ref "U2") (pin "25") (pinfunction "NRST_25") (pintype "passive"))
    )
    (net (code "127") (name "3.3V") (class "Default")
      (node (ref "C10") (pin "2") (pinfunction "2_2") (pintype "passive"))
      (node (ref "C11") (pin "2") (pinfunction "2_2") (pintype "passive"))
      (node (ref "C12") (pin "2") (pinfunction "2_2") (pintype "passive"))
      (node (ref "C13") (pin "2") (pinfunction "2_2") (pintype "passive"))
      (node (ref "C4") (pin "1") (pinfunction "1_1") (pintype "passive"))
      (node (ref "C5") (pin "2") (pinfunction "2_2") (pintype "passive"))
      (node (ref "C7") (pin "2") (pinfunction "2_2") (pintype "passive"))
      (node (ref "C8") (pin "2") (pinfunction "2_2") (pintype "passive"))
      (node (ref "C9") (pin "2") (pinfunction "2_2") (pintype "passive"))
      (node (ref "FLASH1") (pin "3") (pinfunction "WP_3") (pintype "passive"))
      (node (ref "FLASH1") (pin "7") (pinfunction "HOLD_7") (pintype "passive"))
      (node (ref "FLASH1") (pin "8") (pinfunction "VCC_8") (pintype "passive"))
      (node (ref "OV1") (pin "2") (pinfunction "3V3_2") (pintype "passive"))
      (node (ref "P4") (pin "2") (pinfunction "2_2") (pintype "passive"))
      (node (ref "P5") (pin "1") (pinfunction "1_1") (pintype "passive"))
      (node (ref "P5") (pin "2") (pinfunction "2_2") (pintype "passive"))
      (node (ref "P5") (pin "3") (pinfunction "3_3") (pintype "passive"))
      (node (ref "P5") (pin "4") (pinfunction "4_4") (pintype "passive"))
      (node (ref "P5") (pin "5") (pinfunction "5_5") (pintype "passive"))
      (node (ref "P5") (pin "6") (pinfunction "6_6") (pintype "passive"))
      (node (ref "Q4") (pin "3") (pinfunction "C_3") (pintype "passive"))
      (node (ref "R1") (pin "1") (pinfunction "1_1") (pintype "passive"))
      (node (ref "R12") (pin "2") (pinfunction "2_2") (pintype "passive"))
      (node (ref "R2") (pin "1") (pinfunction "1_1") (pintype "passive"))
      (node (ref "R5") (pin "1") (pinfunction "1_1") (pintype "passive"))
      (node (ref "R6") (pin "1") (pinfunction "1_1") (pintype "passive"))
      (node (ref "R9") (pin "1") (pintype "passive"))
      (node (ref "TF1") (pin "4") (pinfunction "VDD_4") (pintype "passive"))
      (node (ref "TFT_LCD1") (pin "24") (pinfunction "VDD_24") (pintype "passive"))
      (node (ref "TFT_LCD1") (pin "25") (pinfunction "VDD_25") (pintype "passive"))
      (node (ref "U1") (pin "3") (pinfunction "VDD_3") (pintype "passive"))
      (node (ref "U2") (pin "108") (pinfunction "Vdd_2_108") (pintype "passive"))
      (node (ref "U2") (pin "121") (pinfunction "Vdd_10_121") (pintype "passive"))
      (node (ref "U2") (pin "131") (pinfunction "Vdd_11_131") (pintype "passive"))
      (node (ref "U2") (pin "144") (pinfunction "Vdd_3_144") (pintype "passive"))
      (node (ref "U2") (pin "17") (pinfunction "Vdd_5_17") (pintype "passive"))
      (node (ref "U2") (pin "32") (pinfunction "Vref+_32") (pintype "passive"))
      (node (ref "U2") (pin "33") (pinfunction "VDDA_33") (pintype "passive"))
      (node (ref "U2") (pin "39") (pinfunction "Vdd_4_39") (pintype "passive"))
      (node (ref "U2") (pin "52") (pinfunction "Vdd_6_52") (pintype "passive"))
      (node (ref "U2") (pin "6") (pinfunction "VBAT_6") (pintype "passive"))
      (node (ref "U2") (pin "62") (pinfunction "Vdd_7_62") (pintype "passive"))
      (node (ref "U2") (pin "72") (pinfunction "Vdd_1_72") (pintype "passive"))
      (node (ref "U2") (pin "84") (pinfunction "Vdd_8_84") (pintype "passive"))
      (node (ref "U2") (pin "95") (pinfunction "Vdd_9_95") (pintype "passive"))
      (node (ref "U3") (pin "1") (pinfunction "VDD_1") (pintype "passive"))
      (node (ref "U3") (pin "12") (pinfunction "SDO/ALT_12") (pintype "passive"))
      (node (ref "U3") (pin "6") (pinfunction "VS_6") (pintype "passive"))
      (node (ref "U3") (pin "7") (pinfunction "~{CS}_7") (pintype "passive"))
      (node (ref "U5") (pin "2") (pinfunction "OUT_2") (pintype "passive"))
      (node (ref "U5") (pin "4") (pinfunction "OUT_4") (pintype "passive"))
    )
    (net (code "128") (name "DGND") (class "Default")
      (node (ref "C1") (pin "2") (pinfunction "2_2") (pintype "passive"))
      (node (ref "C10") (pin "1") (pinfunction "1_1") (pintype "passive"))
      (node (ref "C11") (pin "1") (pinfunction "1_1") (pintype "passive"))
      (node (ref "C12") (pin "1") (pinfunction "1_1") (pintype "passive"))
      (node (ref "C13") (pin "1") (pinfunction "1_1") (pintype "passive"))
      (node (ref "C14") (pin "1") (pinfunction "1_1") (pintype "passive"))
      (node (ref "C15") (pin "1") (pinfunction "1_1") (pintype "passive"))
      (node (ref "C16") (pin "1") (pinfunction "1_1") (pintype "passive"))
      (node (ref "C17") (pin "1") (pinfunction "1_1") (pintype "passive"))
      (node (ref "C18") (pin "1") (pinfunction "1_1") (pintype "passive"))
      (node (ref "C2") (pin "1") (pinfunction "1_1") (pintype "passive"))
      (node (ref "C3") (pin "1") (pinfunction "1_1") (pintype "passive"))
      (node (ref "C5") (pin "1") (pinfunction "1_1") (pintype "passive"))
      (node (ref "C6") (pin "2") (pinfunction "2_2") (pintype "passive"))
      (node (ref "C7") (pin "1") (pinfunction "1_1") (pintype "passive"))
      (node (ref "C8") (pin "1") (pinfunction "1_1") (pintype "passive"))
      (node (ref "C9") (pin "1") (pinfunction "1_1") (pintype "passive"))
      (node (ref "CH1") (pin "1") (pinfunction "GND_1") (pintype "passive"))
      (node (ref "D1") (pin "2") (pinfunction "K_2") (pintype "passive"))
      (node (ref "FLASH1") (pin "4") (pinfunction "GND_4") (pintype "passive"))
      (node (ref "J1") (pin "4") (pinfunction "VSS_4") (pintype "passive"))
      (node (ref "J2") (pin "2") (pinfunction "1_2") (pintype "passive"))
      (node (ref "K1") (pin "1") (pinfunction "1_1") (pintype "passive"))
      (node (ref "OV1") (pin "20") (pinfunction "GND_20") (pintype "passive"))
      (node (ref "P4") (pin "5") (pinfunction "5_5") (pintype "passive"))
      (node (ref "P4") (pin "6") (pinfunction "6_6") (pintype "passive"))
      (node (ref "P6") (pin "1") (pinfunction "1_1") (pintype "passive"))
      (node (ref "P6") (pin "2") (pinfunction "2_2") (pintype "passive"))
      (node (ref "P6") (pin "3") (pinfunction "3_3") (pintype "passive"))
      (node (ref "P6") (pin "4") (pinfunction "4_4") (pintype "passive"))
      (node (ref "P6") (pin "5") (pinfunction "5_5") (pintype "passive"))
      (node (ref "P6") (pin "6") (pinfunction "6_6") (pintype "passive"))
      (node (ref "Q3") (pin "2") (pinfunction "E_2") (pintype "passive"))
      (node (ref "R10") (pin "1") (pinfunction "1_1") (pintype "passive"))
      (node (ref "R7") (pin "1") (pinfunction "1_1") (pintype "passive"))
      (node (ref "R8") (pin "1") (pinfunction "1_1") (pintype "passive"))
      (node (ref "R9") (pin "2") (pintype "passive"))
      (node (ref "TF1") (pin "6") (pinfunction "VSS_6") (pintype "passive"))
      (node (ref "TFT_LCD1") (pin "26") (pinfunction "GND_26") (pintype "passive"))
      (node (ref "TFT_LCD1") (pin "27") (pinfunction "GND_27") (pintype "passive"))
      (node (ref "U1") (pin "1") (pinfunction "GND_1") (pintype "passive"))
      (node (ref "U2") (pin "107") (pinfunction "Vss_2_107") (pintype "passive"))
      (node (ref "U2") (pin "120") (pinfunction "Vss_10_120") (pintype "passive"))
      (node (ref "U2") (pin "130") (pinfunction "Vss_11_130") (pintype "passive"))
      (node (ref "U2") (pin "143") (pinfunction "Vss_3_143") (pintype "passive"))
      (node (ref "U2") (pin "16") (pinfunction "Vss_5_16") (pintype "passive"))
      (node (ref "U2") (pin "30") (pinfunction "VSSA_30") (pintype "passive"))
      (node (ref "U2") (pin "31") (pinfunction "Vref-_31") (pintype "passive"))
      (node (ref "U2") (pin "38") (pinfunction "Vss_4_38") (pintype "passive"))
      (node (ref "U2") (pin "51") (pinfunction "Vss_6_51") (pintype "passive"))
      (node (ref "U2") (pin "61") (pinfunction "Vss_7_61") (pintype "passive"))
      (node (ref "U2") (pin "71") (pinfunction "Vss_1_71") (pintype "passive"))
      (node (ref "U2") (pin "83") (pinfunction "Vss_8_83") (pintype "passive"))
      (node (ref "U2") (pin "94") (pinfunction "Vss_9_94") (pintype "passive"))
      (node (ref "U3") (pin "10") (pinfunction "NC_10") (pintype "passive"))
      (node (ref "U3") (pin "2") (pinfunction "GND1_2") (pintype "passive"))
      (node (ref "U3") (pin "4") (pinfunction "GND2_4") (pintype "passive"))
      (node (ref "U3") (pin "5") (pinfunction "GND3_5") (pintype "passive"))
      (node (ref "U4") (pin "8") (pinfunction "GND_8") (pintype "passive"))
      (node (ref "U5") (pin "1") (pinfunction "GND_1") (pintype "passive"))
    )
    (net (code "129") (name "Net-(CH1-UD+)") (class "Default")
      (node (ref "CH1") (pin "5") (pinfunction "UD+_5") (pintype "passive"))
      (node (ref "J1") (pin "3") (pinfunction "D+_3") (pintype "passive"))
    )
    (net (code "130") (name "Net-(CH1-UD-)") (class "Default")
      (node (ref "CH1") (pin "6") (pinfunction "UD-_6") (pintype "passive"))
      (node (ref "J1") (pin "2") (pinfunction "D-_2") (pintype "passive"))
    )
    (net (code "131") (name "Net-(CH1-V3)") (class "Default")
      (node (ref "C1") (pin "1") (pinfunction "1_1") (pintype "passive"))
      (node (ref "CH1") (pin "4") (pinfunction "V3_4") (pintype "passive"))
    )
    (net (code "132") (name "Net-(D1-A)") (class "Default")
      (node (ref "D1") (pin "1") (pinfunction "A_1") (pintype "passive"))
      (node (ref "R1") (pin "2") (pinfunction "2_2") (pintype "passive"))
    )
    (net (code "133") (name "Net-(J2-0)") (class "Default")
      (node (ref "J2") (pin "1") (pinfunction "0_1") (pintype "passive"))
      (node (ref "Q2") (pin "2") (pinfunction "E_2") (pintype "passive"))
    )
    (net (code "134") (name "Net-(Q3-B)") (class "Default")
      (node (ref "C4") (pin "2") (pinfunction "2_2") (pintype "passive"))
      (node (ref "Q3") (pin "1") (pinfunction "B_1") (pintype "passive"))
      (node (ref "R3") (pin "1") (pinfunction "1_1") (pintype "passive"))
    )
    (net (code "135") (name "Net-(Q4-B)") (class "Default")
      (node (ref "Q4") (pin "1") (pinfunction "B_1") (pintype "passive"))
      (node (ref "R4") (pin "1") (pinfunction "1_1") (pintype "passive"))
    )
    (net (code "136") (name "Net-(Q5-E)") (class "Default")
      (node (ref "Q5") (pin "2") (pinfunction "E_2") (pintype "passive"))
      (node (ref "R11") (pin "1") (pinfunction "1_1") (pintype "passive"))
    )
    (net (code "137") (name "Net-(Q6-B)") (class "Default")
      (node (ref "Q6") (pin "1") (pinfunction "B_1") (pintype "passive"))
      (node (ref "R10") (pin "2") (pinfunction "2_2") (pintype "passive"))
      (node (ref "R11") (pin "2") (pinfunction "2_2") (pintype "passive"))
    )
    (net (code "138") (name "Net-(Q6-C)") (class "Default")
      (node (ref "P4") (pin "1") (pinfunction "1_1") (pintype "passive"))
      (node (ref "Q6") (pin "3") (pinfunction "C_3") (pintype "passive"))
    )
    (net (code "139") (name "Net-(S1-NO)") (class "Default")
      (node (ref "S1") (pin "2") (pinfunction "NO_2") (pintype "passive"))
      (node (ref "U4") (pin "6") (pinfunction "VCC_6") (pintype "passive"))
    )
    (net (code "140") (name "Net-(U2-PB2{slash}BOOT1)") (class "Default")
      (node (ref "R8") (pin "2") (pinfunction "2_2") (pintype "passive"))
      (node (ref "U2") (pin "48") (pinfunction "PB2/BOOT1_48") (pintype "passive"))
    )
    (net (code "141") (name "Net-(U4-MCLK0{slash}RST{slash}P5.4)") (class "Default")
      (node (ref "P2") (pin "2") (pinfunction "2_2") (pintype "passive"))
      (node (ref "U4") (pin "5") (pinfunction "MCLK0/RST/P5.4_5") (pintype "passive"))
    )
    (net (code "142") (name "Net-(U4-MISO{slash}ADC4{slash}P1.4)") (class "Default")
      (node (ref "P2") (pin "4") (pinfunction "4_4") (pintype "passive"))
      (node (ref "U4") (pin "3") (pinfunction "MISO/ADC4/P1.4_3") (pintype "passive"))
    )
    (net (code "143") (name "Net-(U4-MOSI{slash}ADC3{slash}P1.3)") (class "Default")
      (node (ref "P2") (pin "5") (pinfunction "5_5") (pintype "passive"))
      (node (ref "U4") (pin "2") (pinfunction "MOSI/ADC3/P1.3_2") (pintype "passive"))
    )
    (net (code "144") (name "Net-(U4-P1.1{slash}ADC1)") (class "Default")
      (node (ref "P3") (pin "1") (pinfunction "1_1") (pintype "passive"))
      (node (ref "U4") (pin "16") (pinfunction "P1.1/ADC1_16") (pintype "passive"))
    )
    (net (code "145") (name "Net-(U4-P3.7{slash}INT3)") (class "Default")
      (node (ref "P3") (pin "3") (pinfunction "3_3") (pintype "passive"))
      (node (ref "U4") (pin "14") (pinfunction "P3.7/INT3_14") (pintype "passive"))
    )
    (net (code "146") (name "Net-(U4-P5.5)") (class "Default")
      (node (ref "P2") (pin "1") (pinfunction "1_1") (pintype "passive"))
      (node (ref "U4") (pin "7") (pinfunction "P5.5_7") (pintype "passive"))
    )
    (net (code "147") (name "Net-(U4-SCLK{slash}ADC5{slash}P1.5)") (class "Default")
      (node (ref "P2") (pin "3") (pinfunction "3_3") (pintype "passive"))
      (node (ref "U4") (pin "4") (pinfunction "SCLK/ADC5/P1.5_4") (pintype "passive"))
    )
    (net (code "148") (name "Net-(U4-SS{slash}ADC2{slash}P1.2)") (class "Default")
      (node (ref "P2") (pin "6") (pinfunction "6_6") (pintype "passive"))
      (node (ref "U4") (pin "1") (pinfunction "SS/ADC2/P1.2_1") (pintype "passive"))
    )
    (net (code "149") (name "VCC") (class "Default")
      (node (ref "C6") (pin "1") (pinfunction "1_1") (pintype "passive"))
      (node (ref "CH1") (pin "16") (pinfunction "VCC_16") (pintype "passive"))
      (node (ref "J1") (pin "1") (pinfunction "VCC_1") (pintype "passive"))
      (node (ref "P7") (pin "1") (pinfunction "1_1") (pintype "passive"))
      (node (ref "P7") (pin "2") (pinfunction "2_2") (pintype "passive"))
      (node (ref "P7") (pin "3") (pinfunction "3_3") (pintype "passive"))
      (node (ref "P7") (pin "4") (pinfunction "4_4") (pintype "passive"))
      (node (ref "P7") (pin "5") (pinfunction "5_5") (pintype "passive"))
      (node (ref "P7") (pin "6") (pinfunction "6_6") (pintype "passive"))
      (node (ref "Q1") (pin "3") (pinfunction "C_3") (pintype "passive"))
      (node (ref "Q2") (pin "3") (pinfunction "C_3") (pintype "passive"))
      (node (ref "Q5") (pin "3") (pinfunction "C_3") (pintype "passive"))
      (node (ref "Q6") (pin "2") (pinfunction "E_2") (pintype "passive"))
      (node (ref "S1") (pin "1") (pinfunction "COMMON_1") (pintype "passive"))
      (node (ref "U5") (pin "3") (pinfunction "IN_3") (pintype "passive"))
    )
    (net (code "150") (name "unconnected-(CH1-CTS#-Pad9)") (class "Default")
      (node (ref "CH1") (pin "9") (pinfunction "CTS#_9") (pintype "passive"))
    )
    (net (code "151") (name "unconnected-(CH1-DCD#-Pad12)") (class "Default")
      (node (ref "CH1") (pin "12") (pinfunction "DCD#_12") (pintype "passive"))
    )
    (net (code "152") (name "unconnected-(CH1-DSR#-Pad10)") (class "Default")
      (node (ref "CH1") (pin "10") (pinfunction "DSR#_10") (pintype "passive"))
    )
    (net (code "153") (name "unconnected-(CH1-R232-Pad15)") (class "Default")
      (node (ref "CH1") (pin "15") (pinfunction "R232_15") (pintype "passive"))
    )
    (net (code "154") (name "unconnected-(CH1-RI#-Pad11)") (class "Default")
      (node (ref "CH1") (pin "11") (pinfunction "RI#_11") (pintype "passive"))
    )
    (net (code "155") (name "unconnected-(J1-SHELL-Pad5)") (class "Default")
      (node (ref "J1") (pin "5") (pinfunction "SHELL_5") (pintype "passive+no_connect"))
    )
    (net (code "156") (name "unconnected-(J1-SHELL-Pad6)") (class "Default")
      (node (ref "J1") (pin "6") (pinfunction "SHELL_6") (pintype "passive+no_connect"))
    )
    (net (code "157") (name "unconnected-(OV1-HR-Pad18)") (class "Default")
      (node (ref "OV1") (pin "18") (pinfunction "HR_18") (pintype "passive+no_connect"))
    )
    (net (code "158") (name "unconnected-(OV1-NC-Pad10)") (class "Default")
      (node (ref "OV1") (pin "10") (pinfunction "NC_10") (pintype "passive+no_connect"))
    )
    (net (code "159") (name "unconnected-(P8-Pad1)") (class "Default")
      (node (ref "P8") (pin "1") (pinfunction "1_1") (pintype "passive"))
    )
    (net (code "160") (name "unconnected-(P8-Pad2)") (class "Default")
      (node (ref "P8") (pin "2") (pinfunction "2_2") (pintype "passive"))
    )
    (net (code "161") (name "unconnected-(P8-Pad3)") (class "Default")
      (node (ref "P8") (pin "3") (pinfunction "3_3") (pintype "passive"))
    )
    (net (code "162") (name "unconnected-(P8-Pad4)") (class "Default")
      (node (ref "P8") (pin "4") (pinfunction "4_4") (pintype "passive"))
    )
    (net (code "163") (name "unconnected-(TF1-D1-Pad8)") (class "Default")
      (node (ref "TF1") (pin "8") (pinfunction "D1_8") (pintype "passive+no_connect"))
    )
    (net (code "164") (name "unconnected-(TF1-D2-Pad1)") (class "Default")
      (node (ref "TF1") (pin "1") (pinfunction "D2_1") (pintype "passive+no_connect"))
    )
    (net (code "165") (name "unconnected-(TF1-GND-Pad9)") (class "Default")
      (node (ref "TF1") (pin "9") (pinfunction "GND_9") (pintype "passive+no_connect"))
    )
    (net (code "166") (name "unconnected-(TFT_LCD1-5V-Pad28)") (class "Default")
      (node (ref "TFT_LCD1") (pin "28") (pinfunction "5V_28") (pintype "passive+no_connect"))
    )
    (net (code "167") (name "unconnected-(TFT_LCD1-F_CS-Pad32)") (class "Default")
      (node (ref "TFT_LCD1") (pin "32") (pinfunction "F_CS_32") (pintype "passive+no_connect"))
    )
    (net (code "168") (name "unconnected-(TFT_LCD1-PEN-Pad31)") (class "Default")
      (node (ref "TFT_LCD1") (pin "31") (pinfunction "PEN_31") (pintype "passive+no_connect"))
    )
    (net (code "169") (name "unconnected-(TFT_LCD1-SD_CS-Pad22)") (class "Default")
      (node (ref "TFT_LCD1") (pin "22") (pinfunction "SD_CS_22") (pintype "passive+no_connect"))
    )
    (net (code "170") (name "unconnected-(U2-NC-Pad106)") (class "Default")
      (node (ref "U2") (pin "106") (pinfunction "NC_106") (pintype "passive+no_connect"))
    )
    (net (code "171") (name "unconnected-(U2-PC13-TAMPER-RTC-Pad7)") (class "Default")
      (node (ref "U2") (pin "7") (pinfunction "PC13-TAMPER-RTC_7") (pintype "passive+no_connect"))
    )
    (net (code "172") (name "unconnected-(U3-INT1-Pad8)") (class "Default")
      (node (ref "U3") (pin "8") (pinfunction "INT1_8") (pintype "passive+no_connect"))
    )
    (net (code "173") (name "unconnected-(U3-INT2-Pad9)") (class "Default")
      (node (ref "U3") (pin "9") (pinfunction "INT2_9") (pintype "passive+no_connect"))
    )
    (net (code "174") (name "unconnected-(U3-RES1-Pad3)") (class "Default")
      (node (ref "U3") (pin "3") (pinfunction "RES1_3") (pintype "passive+no_connect"))
    )
    (net (code "175") (name "unconnected-(U3-RES2-Pad11)") (class "Default")
      (node (ref "U3") (pin "11") (pinfunction "RES2_11") (pintype "passive+no_connect"))
    )
  )
)
